# Funkschalter1V0_1.net
KiCad netlist of a schematic drawn in EAGLE
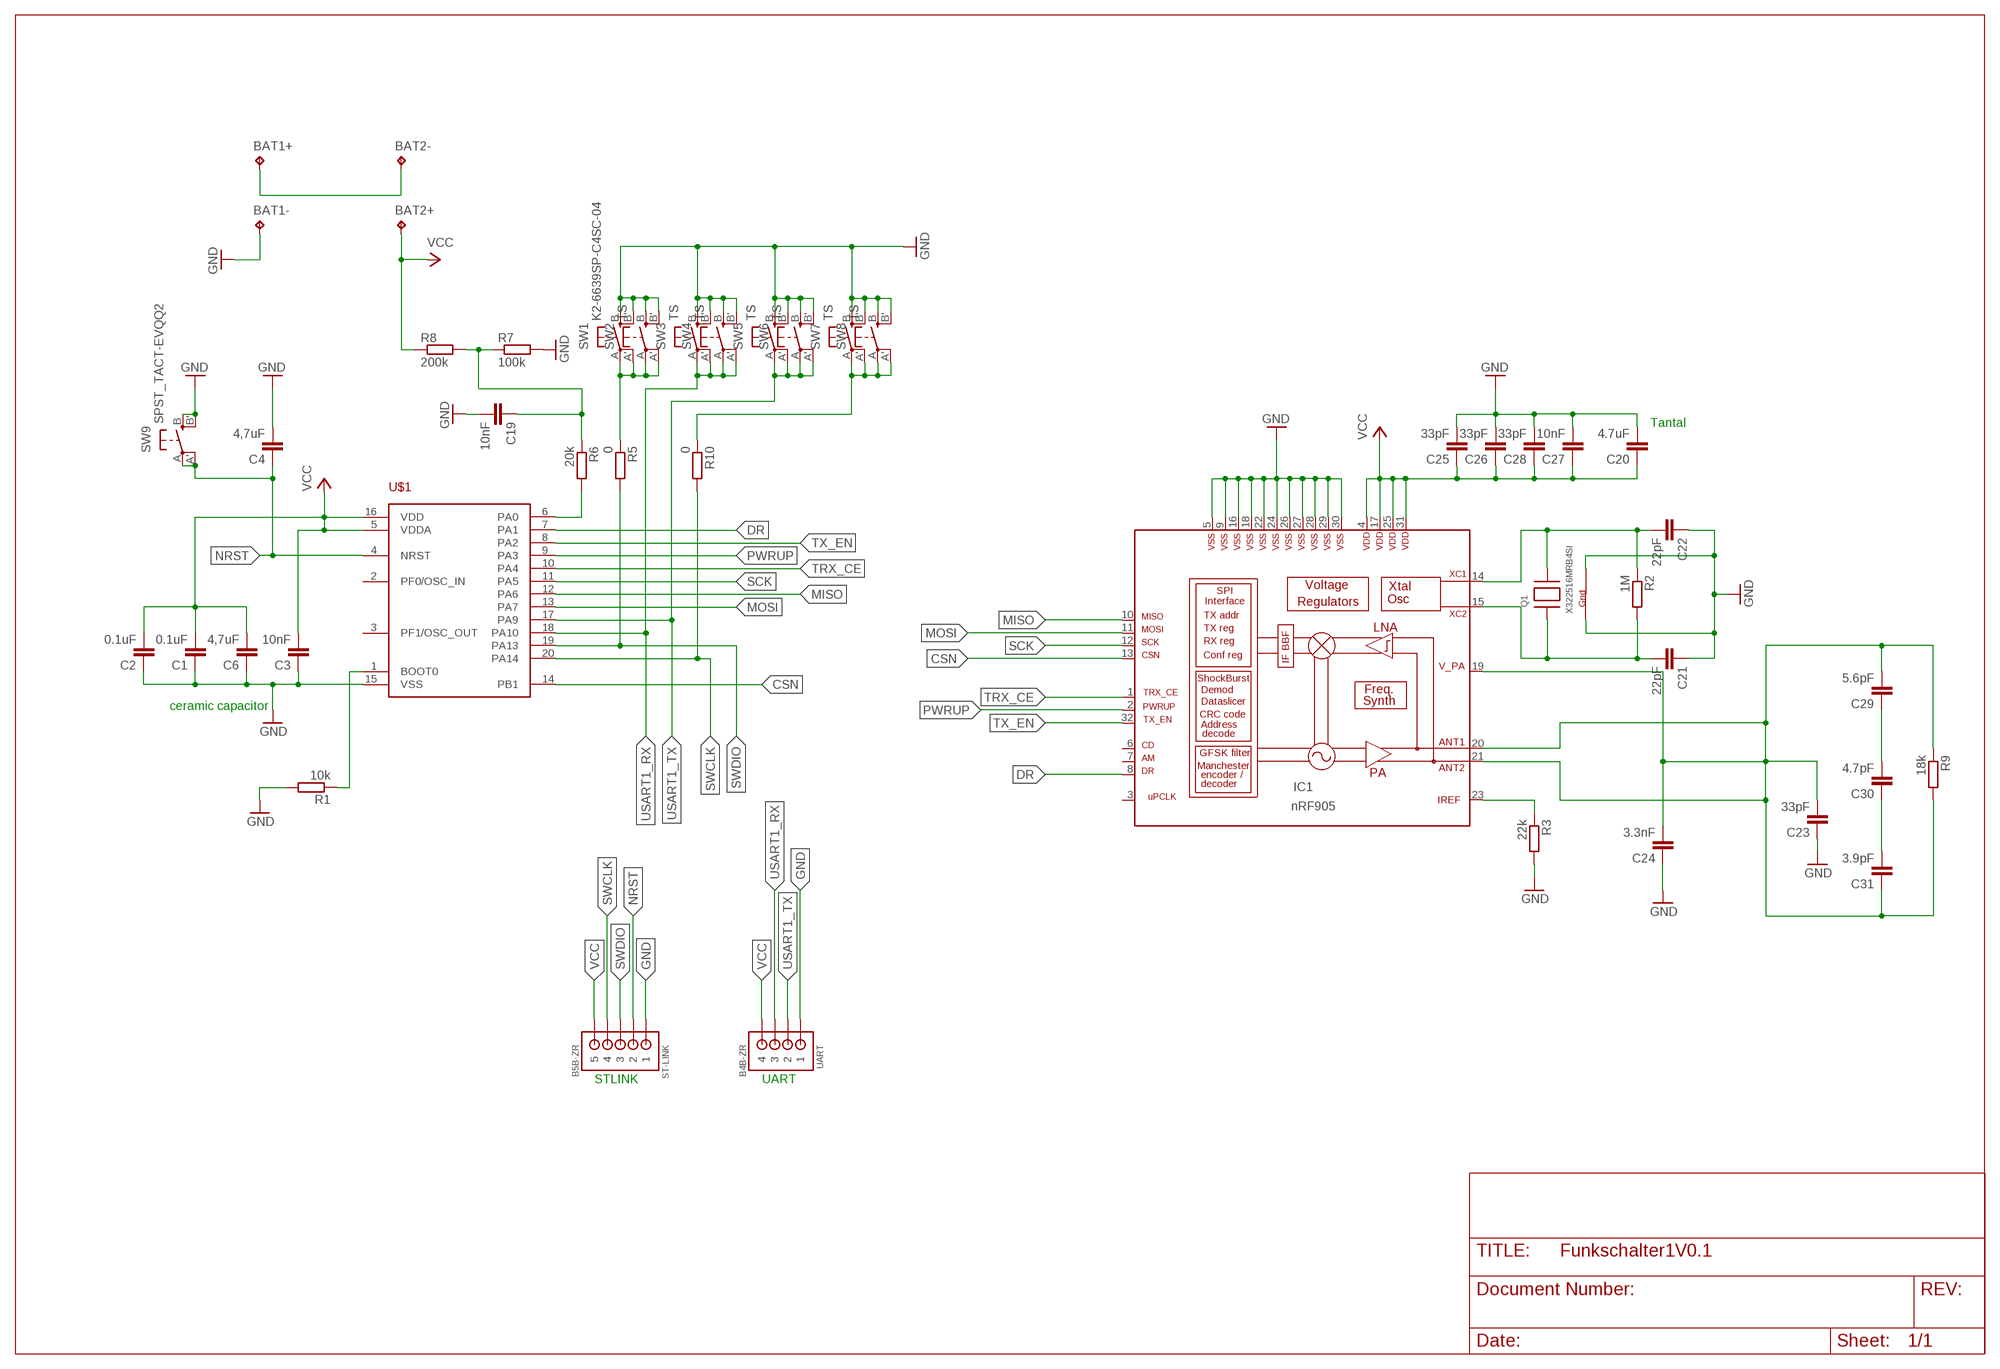
[diagram p0: schematic, sheet 1]

(export (version "E")
  (design (tool "Eeschema 10.0.6"))
  (components
    (comp (ref "BAT1+")
      (value "TPTP20R")
      (footprint "eagle-import:TP20R")
      (libsource (lib "eagle-import") (part "TPTP20R"))
    )
    (comp (ref "BAT1-")
      (value "TPTP20R")
      (footprint "eagle-import:TP20R")
      (libsource (lib "eagle-import") (part "TPTP20R"))
    )
    (comp (ref "BAT2+")
      (value "TPTP20R")
      (footprint "eagle-import:TP20R")
      (libsource (lib "eagle-import") (part "TPTP20R"))
    )
    (comp (ref "BAT2-")
      (value "TPTP20R")
      (footprint "eagle-import:TP20R")
      (libsource (lib "eagle-import") (part "TPTP20R"))
    )
    (comp (ref "C1")
      (value "0.1uF")
      (footprint "eagle-import:C0603")
      (libsource (lib "eagle-import") (part "C-EUC0603"))
    )
    (comp (ref "C2")
      (value "0.1uF")
      (footprint "eagle-import:C0603")
      (libsource (lib "eagle-import") (part "C-EUC0603"))
    )
    (comp (ref "C3")
      (value "10nF")
      (footprint "eagle-import:C0603")
      (libsource (lib "eagle-import") (part "C-EUC0603"))
    )
    (comp (ref "C4")
      (value "4,7uF")
      (footprint "eagle-import:C0603")
      (libsource (lib "eagle-import") (part "C-EUC0603"))
    )
    (comp (ref "C6")
      (value "4,7uF")
      (footprint "eagle-import:C0603")
      (libsource (lib "eagle-import") (part "C-EUC0603"))
    )
    (comp (ref "C19")
      (value "10nF")
      (footprint "eagle-import:C0603")
      (libsource (lib "eagle-import") (part "C-EUC0603"))
    )
    (comp (ref "C20")
      (value "4.7uF")
      (footprint "eagle-import:C0603")
      (libsource (lib "eagle-import") (part "C-EUC0603"))
    )
    (comp (ref "C21")
      (value "22pF")
      (footprint "eagle-import:C0603")
      (libsource (lib "eagle-import") (part "C-EUC0603"))
    )
    (comp (ref "C22")
      (value "22pF")
      (footprint "eagle-import:C0603")
      (libsource (lib "eagle-import") (part "C-EUC0603"))
    )
    (comp (ref "C23")
      (value "33pF")
      (footprint "eagle-import:C0603")
      (libsource (lib "eagle-import") (part "C-EUC0603"))
    )
    (comp (ref "C24")
      (value "3.3nF")
      (footprint "eagle-import:C0603")
      (libsource (lib "eagle-import") (part "C-EUC0603"))
    )
    (comp (ref "C25")
      (value "33pF")
      (footprint "eagle-import:C0603")
      (libsource (lib "eagle-import") (part "C-EUC0603"))
    )
    (comp (ref "C26")
      (value "33pF")
      (footprint "eagle-import:C0603")
      (libsource (lib "eagle-import") (part "C-EUC0603"))
    )
    (comp (ref "C27")
      (value "10nF")
      (footprint "eagle-import:C0603")
      (libsource (lib "eagle-import") (part "C-EUC0603"))
    )
    (comp (ref "C28")
      (value "33pF")
      (footprint "eagle-import:C0603")
      (libsource (lib "eagle-import") (part "C-EUC0603"))
    )
    (comp (ref "C29")
      (value "5.6pF")
      (footprint "eagle-import:C0603")
      (libsource (lib "eagle-import") (part "C-EUC0603"))
    )
    (comp (ref "C30")
      (value "4.7pF")
      (footprint "eagle-import:C0603")
      (libsource (lib "eagle-import") (part "C-EUC0603"))
    )
    (comp (ref "C31")
      (value "3.9pF")
      (footprint "eagle-import:C0603")
      (libsource (lib "eagle-import") (part "C-EUC0603"))
    )
    (comp (ref "IC1")
      (value "nRF905")
      (footprint "eagle-import:QFN32-5X5MM")
      (libsource (lib "eagle-import") (part "NRF905QFN32_5X5MM"))
    )
    (comp (ref "Q1")
      (value "X322516MRB4SI")
      (footprint "eagle-import:NX3225")
      (libsource (lib "eagle-import") (part "XTAL-4-3225"))
    )
    (comp (ref "R1")
      (value "10k")
      (footprint "eagle-import:R0603")
      (libsource (lib "eagle-import") (part "R-EU_R0603"))
    )
    (comp (ref "R2")
      (value "1M")
      (footprint "eagle-import:R0603")
      (libsource (lib "eagle-import") (part "R-EU_R0603"))
    )
    (comp (ref "R3")
      (value "22k")
      (footprint "eagle-import:R0603")
      (libsource (lib "eagle-import") (part "R-EU_R0603"))
    )
    (comp (ref "R5")
      (value "0")
      (footprint "eagle-import:R0603")
      (libsource (lib "eagle-import") (part "R-EU_R0603"))
    )
    (comp (ref "R6")
      (value "20k")
      (footprint "eagle-import:R0603")
      (libsource (lib "eagle-import") (part "R-EU_R0603"))
    )
    (comp (ref "R7")
      (value "100k")
      (footprint "eagle-import:R0603")
      (libsource (lib "eagle-import") (part "R-EU_R0603"))
    )
    (comp (ref "R8")
      (value "200k")
      (footprint "eagle-import:R0603")
      (libsource (lib "eagle-import") (part "R-EU_R0603"))
    )
    (comp (ref "R9")
      (value "18k")
      (footprint "eagle-import:R0603")
      (libsource (lib "eagle-import") (part "R-EU_R0603"))
    )
    (comp (ref "R10")
      (value "0")
      (footprint "eagle-import:R0603")
      (libsource (lib "eagle-import") (part "R-EU_R0603"))
    )
    (comp (ref "ST-LINK")
      (value "B5B-ZR")
      (footprint "eagle-import:B5B-ZR")
      (libsource (lib "eagle-import") (part "B5B-ZR"))
    )
    (comp (ref "SW1")
      (value "K2-6639SP-C4SC-04")
      (footprint "eagle-import:EVQ-Q2")
      (libsource (lib "eagle-import") (part "SPST_TACT-EVQQ2"))
    )
    (comp (ref "SW2")
      (value "TS")
      (footprint "eagle-import:EVQ-Q2")
      (libsource (lib "eagle-import") (part "SPST_TACT-EVQQ2"))
    )
    (comp (ref "SW3")
      (value "TS")
      (footprint "eagle-import:EVQ-Q2")
      (libsource (lib "eagle-import") (part "SPST_TACT-EVQQ2"))
    )
    (comp (ref "SW4")
      (value "TS")
      (footprint "eagle-import:EVQ-Q2")
      (libsource (lib "eagle-import") (part "SPST_TACT-EVQQ2"))
    )
    (comp (ref "SW5")
      (value "TS")
      (footprint "eagle-import:EVQ-Q2")
      (libsource (lib "eagle-import") (part "SPST_TACT-EVQQ2"))
    )
    (comp (ref "SW6")
      (value "TS")
      (footprint "eagle-import:EVQ-Q2")
      (libsource (lib "eagle-import") (part "SPST_TACT-EVQQ2"))
    )
    (comp (ref "SW7")
      (value "TS")
      (footprint "eagle-import:EVQ-Q2")
      (libsource (lib "eagle-import") (part "SPST_TACT-EVQQ2"))
    )
    (comp (ref "SW8")
      (value "TS")
      (footprint "eagle-import:EVQ-Q2")
      (libsource (lib "eagle-import") (part "SPST_TACT-EVQQ2"))
    )
    (comp (ref "SW9")
      (value "SPST_TACT-EVQQ2")
      (footprint "eagle-import:EVQ-Q2")
      (libsource (lib "eagle-import") (part "SPST_TACT-EVQQ2"))
    )
    (comp (ref "U$1")
      (value "STM32F030F4")
      (footprint "eagle-import:TSSOP20")
      (libsource (lib "eagle-import") (part "STM32F030F4"))
    )
    (comp (ref "UART")
      (value "B4B-ZR")
      (footprint "eagle-import:B4B-ZR")
      (libsource (lib "eagle-import") (part "B4B-ZR"))
    )
  )
  (nets
    (net (code "1") (name "CSN") (class "Default")
      (node (ref "IC1") (pin "13") (pinfunction "CSN_13") (pintype "passive"))
      (node (ref "U$1") (pin "14") (pinfunction "PB1_14") (pintype "bidirectional"))
    )
    (net (code "2") (name "DR") (class "Default")
      (node (ref "IC1") (pin "8") (pinfunction "DR_8") (pintype "passive"))
      (node (ref "U$1") (pin "7") (pinfunction "PA1_7") (pintype "bidirectional"))
    )
    (net (code "3") (name "GND") (class "Default")
      (node (ref "BAT1-") (pin "TP") (pinfunction "TP_TP") (pintype "input"))
      (node (ref "C1") (pin "1") (pinfunction "1_1") (pintype "passive"))
      (node (ref "C19") (pin "2") (pinfunction "2_2") (pintype "passive"))
      (node (ref "C2") (pin "1") (pinfunction "1_1") (pintype "passive"))
      (node (ref "C20") (pin "2") (pinfunction "2_2") (pintype "passive"))
      (node (ref "C21") (pin "1") (pinfunction "1_1") (pintype "passive"))
      (node (ref "C22") (pin "1") (pinfunction "1_1") (pintype "passive"))
      (node (ref "C23") (pin "1") (pinfunction "1_1") (pintype "passive"))
      (node (ref "C24") (pin "1") (pinfunction "1_1") (pintype "passive"))
      (node (ref "C25") (pin "2") (pinfunction "2_2") (pintype "passive"))
      (node (ref "C26") (pin "2") (pinfunction "2_2") (pintype "passive"))
      (node (ref "C27") (pin "2") (pinfunction "2_2") (pintype "passive"))
      (node (ref "C28") (pin "2") (pinfunction "2_2") (pintype "passive"))
      (node (ref "C3") (pin "1") (pinfunction "1_1") (pintype "passive"))
      (node (ref "C4") (pin "2") (pinfunction "2_2") (pintype "passive"))
      (node (ref "C6") (pin "1") (pinfunction "1_1") (pintype "passive"))
      (node (ref "IC1") (pin "16") (pinfunction "VSS16_16") (pintype "passive"))
      (node (ref "IC1") (pin "18") (pinfunction "VSS18_18") (pintype "passive"))
      (node (ref "IC1") (pin "22") (pinfunction "VSS22_22") (pintype "passive"))
      (node (ref "IC1") (pin "24") (pinfunction "VSS24_24") (pintype "passive"))
      (node (ref "IC1") (pin "26") (pinfunction "VSS26_26") (pintype "passive"))
      (node (ref "IC1") (pin "27") (pinfunction "VSS27_27") (pintype "passive"))
      (node (ref "IC1") (pin "28") (pinfunction "VSS28_28") (pintype "passive"))
      (node (ref "IC1") (pin "29") (pinfunction "VSS29_29") (pintype "passive"))
      (node (ref "IC1") (pin "30") (pinfunction "VSS30_30") (pintype "passive"))
      (node (ref "IC1") (pin "5") (pinfunction "VSS5_5") (pintype "passive"))
      (node (ref "IC1") (pin "9") (pinfunction "VSS9_9") (pintype "passive"))
      (node (ref "Q1") (pin "2") (pinfunction "G2_2") (pintype "power_in"))
      (node (ref "Q1") (pin "4") (pinfunction "G1_4") (pintype "power_in"))
      (node (ref "R1") (pin "2") (pinfunction "2_2") (pintype "passive"))
      (node (ref "R3") (pin "2") (pinfunction "2_2") (pintype "passive"))
      (node (ref "R7") (pin "2") (pinfunction "2_2") (pintype "passive"))
      (node (ref "ST-LINK") (pin "1") (pinfunction "1_1") (pintype "bidirectional"))
      (node (ref "SW1") (pin "B") (pinfunction "S_B") (pintype "passive"))
      (node (ref "SW1") (pin "B'") (pinfunction "S1_B'") (pintype "passive"))
      (node (ref "SW2") (pin "B") (pinfunction "S_B") (pintype "passive"))
      (node (ref "SW2") (pin "B'") (pinfunction "S1_B'") (pintype "passive"))
      (node (ref "SW3") (pin "B") (pinfunction "S_B") (pintype "passive"))
      (node (ref "SW3") (pin "B'") (pinfunction "S1_B'") (pintype "passive"))
      (node (ref "SW4") (pin "B") (pinfunction "S_B") (pintype "passive"))
      (node (ref "SW4") (pin "B'") (pinfunction "S1_B'") (pintype "passive"))
      (node (ref "SW5") (pin "B") (pinfunction "S_B") (pintype "passive"))
      (node (ref "SW5") (pin "B'") (pinfunction "S1_B'") (pintype "passive"))
      (node (ref "SW6") (pin "B") (pinfunction "S_B") (pintype "passive"))
      (node (ref "SW6") (pin "B'") (pinfunction "S1_B'") (pintype "passive"))
      (node (ref "SW7") (pin "B") (pinfunction "S_B") (pintype "passive"))
      (node (ref "SW7") (pin "B'") (pinfunction "S1_B'") (pintype "passive"))
      (node (ref "SW8") (pin "B") (pinfunction "S_B") (pintype "passive"))
      (node (ref "SW8") (pin "B'") (pinfunction "S1_B'") (pintype "passive"))
      (node (ref "SW9") (pin "B") (pinfunction "S_B") (pintype "passive"))
      (node (ref "SW9") (pin "B'") (pinfunction "S1_B'") (pintype "passive"))
      (node (ref "U$1") (pin "15") (pinfunction "VSS_15") (pintype "bidirectional"))
      (node (ref "UART") (pin "1") (pinfunction "1_1") (pintype "bidirectional"))
    )
    (net (code "4") (name "MISO") (class "Default")
      (node (ref "IC1") (pin "10") (pinfunction "MISO_10") (pintype "passive"))
      (node (ref "U$1") (pin "12") (pinfunction "PA6_12") (pintype "bidirectional"))
    )
    (net (code "5") (name "MOSI") (class "Default")
      (node (ref "IC1") (pin "11") (pinfunction "MOSI_11") (pintype "passive"))
      (node (ref "U$1") (pin "13") (pinfunction "PA7_13") (pintype "bidirectional"))
    )
    (net (code "6") (name "NRST") (class "Default")
      (node (ref "C4") (pin "1") (pinfunction "1_1") (pintype "passive"))
      (node (ref "ST-LINK") (pin "2") (pinfunction "2_2") (pintype "bidirectional"))
      (node (ref "SW9") (pin "A") (pinfunction "P_A") (pintype "passive"))
      (node (ref "SW9") (pin "A'") (pinfunction "P1_A'") (pintype "passive"))
      (node (ref "U$1") (pin "4") (pinfunction "NRST_4") (pintype "bidirectional"))
    )
    (net (code "7") (name "Net-(BAT1+-PadTP)") (class "Default")
      (node (ref "BAT1+") (pin "TP") (pinfunction "TP_TP") (pintype "input"))
      (node (ref "BAT2-") (pin "TP") (pinfunction "TP_TP") (pintype "input"))
    )
    (net (code "8") (name "Net-(C19-Pad1)") (class "Default")
      (node (ref "C19") (pin "1") (pinfunction "1_1") (pintype "passive"))
      (node (ref "R6") (pin "1") (pinfunction "1_1") (pintype "passive"))
      (node (ref "R7") (pin "1") (pinfunction "1_1") (pintype "passive"))
      (node (ref "R8") (pin "2") (pinfunction "2_2") (pintype "passive"))
    )
    (net (code "9") (name "Net-(C29-Pad1)") (class "Default")
      (node (ref "C29") (pin "1") (pinfunction "1_1") (pintype "passive"))
      (node (ref "C30") (pin "2") (pinfunction "2_2") (pintype "passive"))
    )
    (net (code "10") (name "Net-(C30-Pad1)") (class "Default")
      (node (ref "C30") (pin "1") (pinfunction "1_1") (pintype "passive"))
      (node (ref "C31") (pin "2") (pinfunction "2_2") (pintype "passive"))
    )
    (net (code "11") (name "Net-(IC1-ANT1)") (class "Default")
      (node (ref "C23") (pin "2") (pinfunction "2_2") (pintype "passive"))
      (node (ref "C24") (pin "2") (pinfunction "2_2") (pintype "passive"))
      (node (ref "C29") (pin "2") (pinfunction "2_2") (pintype "passive"))
      (node (ref "C31") (pin "1") (pinfunction "1_1") (pintype "passive"))
      (node (ref "IC1") (pin "19") (pinfunction "VDD_PA_19") (pintype "power_in"))
      (node (ref "IC1") (pin "20") (pinfunction "ANT1_20") (pintype "passive"))
      (node (ref "IC1") (pin "21") (pinfunction "ANT2_21") (pintype "passive"))
      (node (ref "R9") (pin "1") (pinfunction "1_1") (pintype "passive"))
      (node (ref "R9") (pin "2") (pinfunction "2_2") (pintype "passive"))
    )
    (net (code "12") (name "Net-(IC1-IREF)") (class "Default")
      (node (ref "IC1") (pin "23") (pinfunction "IREF_23") (pintype "passive"))
      (node (ref "R3") (pin "1") (pinfunction "1_1") (pintype "passive"))
    )
    (net (code "13") (name "Net-(IC1-XC1)") (class "Default")
      (node (ref "C22") (pin "2") (pinfunction "2_2") (pintype "passive"))
      (node (ref "IC1") (pin "14") (pinfunction "XC1_14") (pintype "passive"))
      (node (ref "Q1") (pin "3") (pinfunction "X2_3") (pintype "bidirectional"))
      (node (ref "R2") (pin "1") (pinfunction "1_1") (pintype "passive"))
    )
    (net (code "14") (name "Net-(IC1-XC2)") (class "Default")
      (node (ref "C21") (pin "2") (pinfunction "2_2") (pintype "passive"))
      (node (ref "IC1") (pin "15") (pinfunction "XC2_15") (pintype "passive"))
      (node (ref "Q1") (pin "1") (pinfunction "X1_1") (pintype "bidirectional"))
      (node (ref "R2") (pin "2") (pinfunction "2_2") (pintype "passive"))
    )
    (net (code "15") (name "Net-(SW1-P)") (class "Default")
      (node (ref "R5") (pin "1") (pinfunction "1_1") (pintype "passive"))
      (node (ref "SW1") (pin "A") (pinfunction "P_A") (pintype "passive"))
      (node (ref "SW1") (pin "A'") (pinfunction "P1_A'") (pintype "passive"))
      (node (ref "SW2") (pin "A") (pinfunction "P_A") (pintype "passive"))
      (node (ref "SW2") (pin "A'") (pinfunction "P1_A'") (pintype "passive"))
    )
    (net (code "16") (name "Net-(SW7-P)") (class "Default")
      (node (ref "R10") (pin "1") (pinfunction "1_1") (pintype "passive"))
      (node (ref "SW7") (pin "A") (pinfunction "P_A") (pintype "passive"))
      (node (ref "SW7") (pin "A'") (pinfunction "P1_A'") (pintype "passive"))
      (node (ref "SW8") (pin "A") (pinfunction "P_A") (pintype "passive"))
      (node (ref "SW8") (pin "A'") (pinfunction "P1_A'") (pintype "passive"))
    )
    (net (code "17") (name "Net-(U$1-BOOT0)") (class "Default")
      (node (ref "R1") (pin "1") (pinfunction "1_1") (pintype "passive"))
      (node (ref "U$1") (pin "1") (pinfunction "BOOT0_1") (pintype "bidirectional"))
    )
    (net (code "18") (name "Net-(U$1-PA0)") (class "Default")
      (node (ref "R6") (pin "2") (pinfunction "2_2") (pintype "passive"))
      (node (ref "U$1") (pin "6") (pinfunction "PA0_6") (pintype "bidirectional"))
    )
    (net (code "19") (name "PWRUP") (class "Default")
      (node (ref "IC1") (pin "2") (pinfunction "PWR_UP_2") (pintype "passive"))
      (node (ref "U$1") (pin "9") (pinfunction "PA3_9") (pintype "bidirectional"))
    )
    (net (code "20") (name "SCK") (class "Default")
      (node (ref "IC1") (pin "12") (pinfunction "SCK_12") (pintype "passive"))
      (node (ref "U$1") (pin "11") (pinfunction "PA5_11") (pintype "bidirectional"))
    )
    (net (code "21") (name "SWCLK") (class "Default")
      (node (ref "R10") (pin "2") (pinfunction "2_2") (pintype "passive"))
      (node (ref "ST-LINK") (pin "4") (pinfunction "4_4") (pintype "bidirectional"))
      (node (ref "U$1") (pin "20") (pinfunction "PA14_20") (pintype "bidirectional"))
    )
    (net (code "22") (name "SWDIO") (class "Default")
      (node (ref "R5") (pin "2") (pinfunction "2_2") (pintype "passive"))
      (node (ref "ST-LINK") (pin "3") (pinfunction "3_3") (pintype "bidirectional"))
      (node (ref "U$1") (pin "19") (pinfunction "PA13_19") (pintype "bidirectional"))
    )
    (net (code "23") (name "TRX_CE") (class "Default")
      (node (ref "IC1") (pin "1") (pinfunction "TRX_CE_1") (pintype "passive"))
      (node (ref "U$1") (pin "10") (pinfunction "PA4_10") (pintype "bidirectional"))
    )
    (net (code "24") (name "TX_EN") (class "Default")
      (node (ref "IC1") (pin "32") (pinfunction "TX_EN_32") (pintype "passive"))
      (node (ref "U$1") (pin "8") (pinfunction "PA2_8") (pintype "bidirectional"))
    )
    (net (code "25") (name "USART1_RX") (class "Default")
      (node (ref "SW3") (pin "A") (pinfunction "P_A") (pintype "passive"))
      (node (ref "SW3") (pin "A'") (pinfunction "P1_A'") (pintype "passive"))
      (node (ref "SW4") (pin "A") (pinfunction "P_A") (pintype "passive"))
      (node (ref "SW4") (pin "A'") (pinfunction "P1_A'") (pintype "passive"))
      (node (ref "U$1") (pin "18") (pinfunction "PA10_18") (pintype "bidirectional"))
      (node (ref "UART") (pin "3") (pinfunction "3_3") (pintype "bidirectional"))
    )
    (net (code "26") (name "USART1_TX") (class "Default")
      (node (ref "SW5") (pin "A") (pinfunction "P_A") (pintype "passive"))
      (node (ref "SW5") (pin "A'") (pinfunction "P1_A'") (pintype "passive"))
      (node (ref "SW6") (pin "A") (pinfunction "P_A") (pintype "passive"))
      (node (ref "SW6") (pin "A'") (pinfunction "P1_A'") (pintype "passive"))
      (node (ref "U$1") (pin "17") (pinfunction "PA9_17") (pintype "bidirectional"))
      (node (ref "UART") (pin "2") (pinfunction "2_2") (pintype "bidirectional"))
    )
    (net (code "27") (name "VCC") (class "Default")
      (node (ref "BAT2+") (pin "TP") (pinfunction "TP_TP") (pintype "input"))
      (node (ref "C1") (pin "2") (pinfunction "2_2") (pintype "passive"))
      (node (ref "C2") (pin "2") (pinfunction "2_2") (pintype "passive"))
      (node (ref "C20") (pin "1") (pinfunction "1_1") (pintype "passive"))
      (node (ref "C25") (pin "1") (pinfunction "1_1") (pintype "passive"))
      (node (ref "C26") (pin "1") (pinfunction "1_1") (pintype "passive"))
      (node (ref "C27") (pin "1") (pinfunction "1_1") (pintype "passive"))
      (node (ref "C28") (pin "1") (pinfunction "1_1") (pintype "passive"))
      (node (ref "C3") (pin "2") (pinfunction "2_2") (pintype "passive"))
      (node (ref "C6") (pin "2") (pinfunction "2_2") (pintype "passive"))
      (node (ref "IC1") (pin "17") (pinfunction "VDD17_17") (pintype "power_in"))
      (node (ref "IC1") (pin "25") (pinfunction "VDD25_25") (pintype "power_in"))
      (node (ref "IC1") (pin "31") (pinfunction "DVDD1V2_31") (pintype "passive"))
      (node (ref "IC1") (pin "4") (pinfunction "VDD4_4") (pintype "power_in"))
      (node (ref "R8") (pin "1") (pinfunction "1_1") (pintype "passive"))
      (node (ref "ST-LINK") (pin "5") (pinfunction "5_5") (pintype "bidirectional"))
      (node (ref "U$1") (pin "16") (pinfunction "VDD_16") (pintype "bidirectional"))
      (node (ref "U$1") (pin "5") (pinfunction "VDDA_5") (pintype "bidirectional"))
      (node (ref "UART") (pin "4") (pinfunction "4_4") (pintype "bidirectional"))
    )
    (net (code "28") (name "unconnected-(IC1-AM-Pad7)") (class "Default")
      (node (ref "IC1") (pin "7") (pinfunction "AM_7") (pintype "passive"))
    )
    (net (code "29") (name "unconnected-(IC1-CD-Pad6)") (class "Default")
      (node (ref "IC1") (pin "6") (pinfunction "CD_6") (pintype "passive"))
    )
    (net (code "30") (name "unconnected-(IC1-UPCLK-Pad3)") (class "Default")
      (node (ref "IC1") (pin "3") (pinfunction "UPCLK_3") (pintype "passive"))
    )
    (net (code "31") (name "unconnected-(U$1-PF0{slash}OSC_IN-Pad2)") (class "Default")
      (node (ref "U$1") (pin "2") (pinfunction "PF0/OSC_IN_2") (pintype "bidirectional"))
    )
    (net (code "32") (name "unconnected-(U$1-PF1{slash}OSC_OUT-Pad3)") (class "Default")
      (node (ref "U$1") (pin "3") (pinfunction "PF1/OSC_OUT_3") (pintype "bidirectional"))
    )
  )
)
